# Power_Board.net
KiCad netlist of a schematic drawn in EAGLE
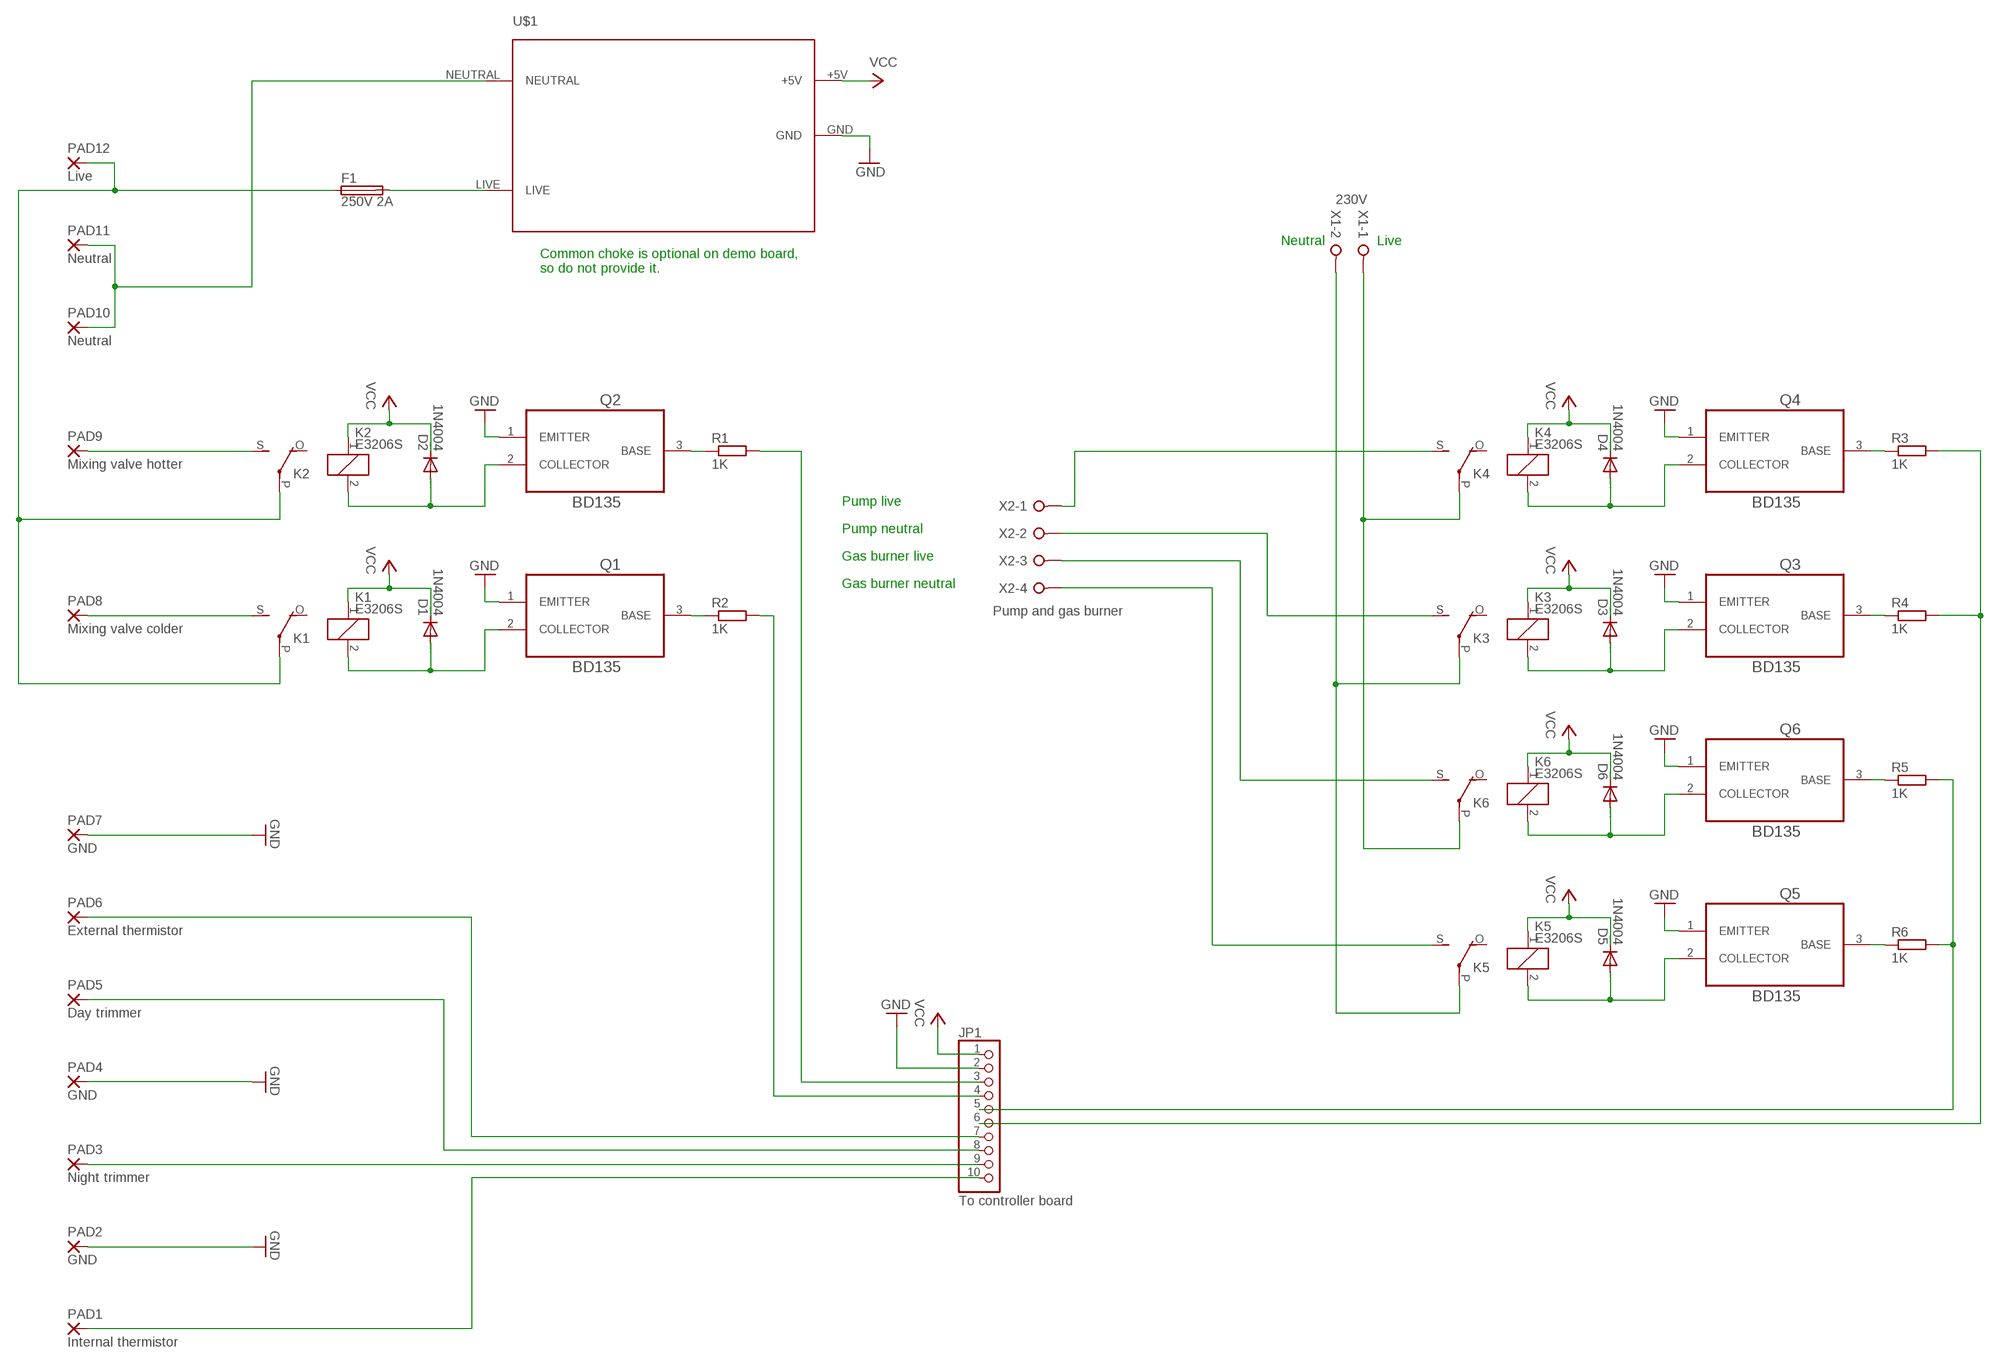
[diagram p0: schematic, sheet 1]

(export (version "E")
  (design (tool "Eeschema 10.0.6"))
  (components
    (comp (ref "D1")
      (value "1N4004")
      (footprint "eagle-import:DO41-10")
      (libsource (lib "eagle-import") (part "1N4004"))
    )
    (comp (ref "D2")
      (value "1N4004")
      (footprint "eagle-import:DO41-10")
      (libsource (lib "eagle-import") (part "1N4004"))
    )
    (comp (ref "D3")
      (value "1N4004")
      (footprint "eagle-import:DO41-10")
      (libsource (lib "eagle-import") (part "1N4004"))
    )
    (comp (ref "D4")
      (value "1N4004")
      (footprint "eagle-import:DO41-10")
      (libsource (lib "eagle-import") (part "1N4004"))
    )
    (comp (ref "D5")
      (value "1N4004")
      (footprint "eagle-import:DO41-10")
      (libsource (lib "eagle-import") (part "1N4004"))
    )
    (comp (ref "D6")
      (value "1N4004")
      (footprint "eagle-import:DO41-10")
      (libsource (lib "eagle-import") (part "1N4004"))
    )
    (comp (ref "F1")
      (value "250V 2A")
      (footprint "eagle-import:GSH15")
      (fields (field (name "MPN") "64900001039"))
      (libsource (lib "eagle-import") (part "GSH15"))
    )
    (comp (ref "JP1")
      (value "To controller board")
      (footprint "eagle-import:1X10")
      (libsource (lib "eagle-import") (part "PINHD-1X10"))
    )
    (comp (ref "K1")
      (value "E3206S")
      (footprint "eagle-import:E3206S")
      (libsource (lib "eagle-import") (part "E3206S"))
    )
    (comp (ref "K2")
      (value "E3206S")
      (footprint "eagle-import:E3206S")
      (libsource (lib "eagle-import") (part "E3206S"))
    )
    (comp (ref "K3")
      (value "E3206S")
      (footprint "eagle-import:E3206S")
      (libsource (lib "eagle-import") (part "E3206S"))
    )
    (comp (ref "K4")
      (value "E3206S")
      (footprint "eagle-import:E3206S")
      (libsource (lib "eagle-import") (part "E3206S"))
    )
    (comp (ref "K5")
      (value "E3206S")
      (footprint "eagle-import:E3206S")
      (libsource (lib "eagle-import") (part "E3206S"))
    )
    (comp (ref "K6")
      (value "E3206S")
      (footprint "eagle-import:E3206S")
      (libsource (lib "eagle-import") (part "E3206S"))
    )
    (comp (ref "PAD1")
      (value "Internal thermistor")
      (footprint "eagle-import:SMD2,54-20,32")
      (libsource (lib "eagle-import") (part "SMD20"))
    )
    (comp (ref "PAD2")
      (value "GND")
      (footprint "eagle-import:SMD2,54-20,32")
      (libsource (lib "eagle-import") (part "SMD20"))
    )
    (comp (ref "PAD3")
      (value "Night trimmer")
      (footprint "eagle-import:SMD2,54-20,32")
      (libsource (lib "eagle-import") (part "SMD20"))
    )
    (comp (ref "PAD4")
      (value "GND")
      (footprint "eagle-import:SMD2,54-20,32")
      (libsource (lib "eagle-import") (part "SMD20"))
    )
    (comp (ref "PAD5")
      (value "Day trimmer")
      (footprint "eagle-import:SMD2,54-20,32")
      (libsource (lib "eagle-import") (part "SMD20"))
    )
    (comp (ref "PAD6")
      (value "External thermistor")
      (footprint "eagle-import:SMD2,54-20,32")
      (libsource (lib "eagle-import") (part "SMD20"))
    )
    (comp (ref "PAD7")
      (value "GND")
      (footprint "eagle-import:SMD2,54-20,32")
      (libsource (lib "eagle-import") (part "SMD20"))
    )
    (comp (ref "PAD8")
      (value "Mixing valve colder")
      (footprint "eagle-import:SMD2,54-20,32")
      (libsource (lib "eagle-import") (part "SMD20"))
    )
    (comp (ref "PAD9")
      (value "Mixing valve hotter")
      (footprint "eagle-import:SMD2,54-20,32")
      (libsource (lib "eagle-import") (part "SMD20"))
    )
    (comp (ref "PAD10")
      (value "Neutral")
      (footprint "eagle-import:SMD2,54-20,32")
      (libsource (lib "eagle-import") (part "SMD20"))
    )
    (comp (ref "PAD11")
      (value "Neutral")
      (footprint "eagle-import:SMD2,54-20,32")
      (libsource (lib "eagle-import") (part "SMD20"))
    )
    (comp (ref "PAD12")
      (value "Live")
      (footprint "eagle-import:SMD2,54-20,32")
      (libsource (lib "eagle-import") (part "SMD20"))
    )
    (comp (ref "Q1")
      (value "BD135")
      (footprint "eagle-import:TRANS_BD135")
      (fields (field (name "MPN") "    BD135"))
      (libsource (lib "eagle-import") (part "BD135"))
    )
    (comp (ref "Q2")
      (value "BD135")
      (footprint "eagle-import:TRANS_BD135")
      (fields (field (name "MPN") "    BD135"))
      (libsource (lib "eagle-import") (part "BD135"))
    )
    (comp (ref "Q3")
      (value "BD135")
      (footprint "eagle-import:TRANS_BD135")
      (fields (field (name "MPN") "    BD135"))
      (libsource (lib "eagle-import") (part "BD135"))
    )
    (comp (ref "Q4")
      (value "BD135")
      (footprint "eagle-import:TRANS_BD135")
      (fields (field (name "MPN") "    BD135"))
      (libsource (lib "eagle-import") (part "BD135"))
    )
    (comp (ref "Q5")
      (value "BD135")
      (footprint "eagle-import:TRANS_BD135")
      (fields (field (name "MPN") "    BD135"))
      (libsource (lib "eagle-import") (part "BD135"))
    )
    (comp (ref "Q6")
      (value "BD135")
      (footprint "eagle-import:TRANS_BD135")
      (fields (field (name "MPN") "    BD135"))
      (libsource (lib "eagle-import") (part "BD135"))
    )
    (comp (ref "R1")
      (value "1K")
      (footprint "eagle-import:0207_10")
      (libsource (lib "eagle-import") (part "R-EU_0207/10"))
    )
    (comp (ref "R2")
      (value "1K")
      (footprint "eagle-import:0207_10")
      (libsource (lib "eagle-import") (part "R-EU_0207/10"))
    )
    (comp (ref "R3")
      (value "1K")
      (footprint "eagle-import:0207_10")
      (libsource (lib "eagle-import") (part "R-EU_0207/10"))
    )
    (comp (ref "R4")
      (value "1K")
      (footprint "eagle-import:0207_10")
      (libsource (lib "eagle-import") (part "R-EU_0207/10"))
    )
    (comp (ref "R5")
      (value "1K")
      (footprint "eagle-import:0207_10")
      (libsource (lib "eagle-import") (part "R-EU_0207/10"))
    )
    (comp (ref "R6")
      (value "1K")
      (footprint "eagle-import:0207_10")
      (libsource (lib "eagle-import") (part "R-EU_0207/10"))
    )
    (comp (ref "U$1")
      (value "VTX-214-010-205")
      (footprint "eagle-import:VTX-214-010-205")
      (libsource (lib "eagle-import") (part "VTX-214-010-205"))
    )
    (comp (ref "X1")
      (value "230V")
      (footprint "eagle-import:W237-132")
      (libsource (lib "eagle-import") (part "W237-02P"))
    )
    (comp (ref "X2")
      (value "Pump and gas burner")
      (footprint "eagle-import:W237-4P")
      (libsource (lib "eagle-import") (part "W237-04P"))
    )
  )
  (nets
    (net (code "1") (name "GND") (class "Default")
      (node (ref "JP1") (pin "2") (pinfunction "2_2") (pintype "passive"))
      (node (ref "PAD2") (pin "1") (pinfunction "P_1") (pintype "passive"))
      (node (ref "PAD4") (pin "1") (pinfunction "P_1") (pintype "passive"))
      (node (ref "PAD7") (pin "1") (pinfunction "P_1") (pintype "passive"))
      (node (ref "Q1") (pin "1") (pinfunction "EMITTER_1") (pintype "passive"))
      (node (ref "Q2") (pin "1") (pinfunction "EMITTER_1") (pintype "passive"))
      (node (ref "Q3") (pin "1") (pinfunction "EMITTER_1") (pintype "passive"))
      (node (ref "Q4") (pin "1") (pinfunction "EMITTER_1") (pintype "passive"))
      (node (ref "Q5") (pin "1") (pinfunction "EMITTER_1") (pintype "passive"))
      (node (ref "Q6") (pin "1") (pinfunction "EMITTER_1") (pintype "passive"))
      (node (ref "U$1") (pin "GND") (pinfunction "GND_GND") (pintype "power_in"))
    )
    (net (code "2") (name "Net-(F1-Pad2)") (class "Default")
      (node (ref "F1") (pin "2") (pinfunction "2_2") (pintype "passive"))
      (node (ref "U$1") (pin "LIVE") (pinfunction "LIVE_LIVE") (pintype "power_in"))
    )
    (net (code "3") (name "Net-(JP1-Pad3)") (class "Default")
      (node (ref "JP1") (pin "3") (pinfunction "3_3") (pintype "passive"))
      (node (ref "R1") (pin "2") (pinfunction "2_2") (pintype "passive"))
    )
    (net (code "4") (name "Net-(JP1-Pad4)") (class "Default")
      (node (ref "JP1") (pin "4") (pinfunction "4_4") (pintype "passive"))
      (node (ref "R2") (pin "2") (pinfunction "2_2") (pintype "passive"))
    )
    (net (code "5") (name "Net-(JP1-Pad5)") (class "Default")
      (node (ref "JP1") (pin "5") (pinfunction "5_5") (pintype "passive"))
      (node (ref "R5") (pin "2") (pinfunction "2_2") (pintype "passive"))
      (node (ref "R6") (pin "2") (pinfunction "2_2") (pintype "passive"))
    )
    (net (code "6") (name "Net-(JP1-Pad6)") (class "Default")
      (node (ref "JP1") (pin "6") (pinfunction "6_6") (pintype "passive"))
      (node (ref "R3") (pin "2") (pinfunction "2_2") (pintype "passive"))
      (node (ref "R4") (pin "2") (pinfunction "2_2") (pintype "passive"))
    )
    (net (code "7") (name "Net-(PAD1-P)") (class "Default")
      (node (ref "JP1") (pin "10") (pinfunction "10_10") (pintype "passive"))
      (node (ref "PAD1") (pin "1") (pinfunction "P_1") (pintype "passive"))
    )
    (net (code "8") (name "Net-(PAD3-P)") (class "Default")
      (node (ref "JP1") (pin "9") (pinfunction "9_9") (pintype "passive"))
      (node (ref "PAD3") (pin "1") (pinfunction "P_1") (pintype "passive"))
    )
    (net (code "9") (name "Net-(PAD5-P)") (class "Default")
      (node (ref "JP1") (pin "8") (pinfunction "8_8") (pintype "passive"))
      (node (ref "PAD5") (pin "1") (pinfunction "P_1") (pintype "passive"))
    )
    (net (code "10") (name "Net-(PAD6-P)") (class "Default")
      (node (ref "JP1") (pin "7") (pinfunction "7_7") (pintype "passive"))
      (node (ref "PAD6") (pin "1") (pinfunction "P_1") (pintype "passive"))
    )
    (net (code "11") (name "Net-(PAD8-P)") (class "Default")
      (node (ref "K1") (pin "S") (pinfunction "S_S") (pintype "passive"))
      (node (ref "PAD8") (pin "1") (pinfunction "P_1") (pintype "passive"))
    )
    (net (code "12") (name "Net-(PAD9-P)") (class "Default")
      (node (ref "K2") (pin "S") (pinfunction "S_S") (pintype "passive"))
      (node (ref "PAD9") (pin "1") (pinfunction "P_1") (pintype "passive"))
    )
    (net (code "13") (name "Net-(PAD10-P)") (class "Default")
      (node (ref "PAD10") (pin "1") (pinfunction "P_1") (pintype "passive"))
      (node (ref "PAD11") (pin "1") (pinfunction "P_1") (pintype "passive"))
      (node (ref "U$1") (pin "NEUTRAL") (pinfunction "NEUTRAL_NEUTRAL") (pintype "power_in"))
    )
    (net (code "14") (name "Net-(PAD12-P)") (class "Default")
      (node (ref "F1") (pin "1") (pinfunction "1_1") (pintype "passive"))
      (node (ref "K1") (pin "P") (pinfunction "P_P") (pintype "passive"))
      (node (ref "K2") (pin "P") (pinfunction "P_P") (pintype "passive"))
      (node (ref "PAD12") (pin "1") (pinfunction "P_1") (pintype "passive"))
    )
    (net (code "15") (name "Net-(Q1-BASE)") (class "Default")
      (node (ref "Q1") (pin "3") (pinfunction "BASE_3") (pintype "passive"))
      (node (ref "R2") (pin "1") (pinfunction "1_1") (pintype "passive"))
    )
    (net (code "16") (name "Net-(Q1-COLLECTOR)") (class "Default")
      (node (ref "D1") (pin "A") (pinfunction "A_A") (pintype "passive"))
      (node (ref "K1") (pin "2") (pinfunction "2_2") (pintype "passive"))
      (node (ref "Q1") (pin "2") (pinfunction "COLLECTOR_2") (pintype "passive"))
    )
    (net (code "17") (name "Net-(Q2-BASE)") (class "Default")
      (node (ref "Q2") (pin "3") (pinfunction "BASE_3") (pintype "passive"))
      (node (ref "R1") (pin "1") (pinfunction "1_1") (pintype "passive"))
    )
    (net (code "18") (name "Net-(Q2-COLLECTOR)") (class "Default")
      (node (ref "D2") (pin "A") (pinfunction "A_A") (pintype "passive"))
      (node (ref "K2") (pin "2") (pinfunction "2_2") (pintype "passive"))
      (node (ref "Q2") (pin "2") (pinfunction "COLLECTOR_2") (pintype "passive"))
    )
    (net (code "19") (name "Net-(Q3-BASE)") (class "Default")
      (node (ref "Q3") (pin "3") (pinfunction "BASE_3") (pintype "passive"))
      (node (ref "R4") (pin "1") (pinfunction "1_1") (pintype "passive"))
    )
    (net (code "20") (name "Net-(Q3-COLLECTOR)") (class "Default")
      (node (ref "D3") (pin "A") (pinfunction "A_A") (pintype "passive"))
      (node (ref "K3") (pin "2") (pinfunction "2_2") (pintype "passive"))
      (node (ref "Q3") (pin "2") (pinfunction "COLLECTOR_2") (pintype "passive"))
    )
    (net (code "21") (name "Net-(Q4-BASE)") (class "Default")
      (node (ref "Q4") (pin "3") (pinfunction "BASE_3") (pintype "passive"))
      (node (ref "R3") (pin "1") (pinfunction "1_1") (pintype "passive"))
    )
    (net (code "22") (name "Net-(Q4-COLLECTOR)") (class "Default")
      (node (ref "D4") (pin "A") (pinfunction "A_A") (pintype "passive"))
      (node (ref "K4") (pin "2") (pinfunction "2_2") (pintype "passive"))
      (node (ref "Q4") (pin "2") (pinfunction "COLLECTOR_2") (pintype "passive"))
    )
    (net (code "23") (name "Net-(Q5-BASE)") (class "Default")
      (node (ref "Q5") (pin "3") (pinfunction "BASE_3") (pintype "passive"))
      (node (ref "R6") (pin "1") (pinfunction "1_1") (pintype "passive"))
    )
    (net (code "24") (name "Net-(Q5-COLLECTOR)") (class "Default")
      (node (ref "D5") (pin "A") (pinfunction "A_A") (pintype "passive"))
      (node (ref "K5") (pin "2") (pinfunction "2_2") (pintype "passive"))
      (node (ref "Q5") (pin "2") (pinfunction "COLLECTOR_2") (pintype "passive"))
    )
    (net (code "25") (name "Net-(Q6-BASE)") (class "Default")
      (node (ref "Q6") (pin "3") (pinfunction "BASE_3") (pintype "passive"))
      (node (ref "R5") (pin "1") (pinfunction "1_1") (pintype "passive"))
    )
    (net (code "26") (name "Net-(Q6-COLLECTOR)") (class "Default")
      (node (ref "D6") (pin "A") (pinfunction "A_A") (pintype "passive"))
      (node (ref "K6") (pin "2") (pinfunction "2_2") (pintype "passive"))
      (node (ref "Q6") (pin "2") (pinfunction "COLLECTOR_2") (pintype "passive"))
    )
    (net (code "27") (name "Net-(X1A-KL)") (class "Default")
      (node (ref "K4") (pin "P") (pinfunction "P_P") (pintype "passive"))
      (node (ref "K6") (pin "P") (pinfunction "P_P") (pintype "passive"))
      (node (ref "X1") (pin "1") (pinfunction "KL_1") (pintype "passive"))
    )
    (net (code "28") (name "Net-(X1B-KL)") (class "Default")
      (node (ref "K3") (pin "P") (pinfunction "P_P") (pintype "passive"))
      (node (ref "K5") (pin "P") (pinfunction "P_P") (pintype "passive"))
      (node (ref "X1") (pin "2") (pinfunction "KL_2") (pintype "passive"))
    )
    (net (code "29") (name "Net-(X2A-KL)") (class "Default")
      (node (ref "K4") (pin "S") (pinfunction "S_S") (pintype "passive"))
      (node (ref "X2") (pin "1") (pinfunction "KL_1") (pintype "passive"))
    )
    (net (code "30") (name "Net-(X2B-KL)") (class "Default")
      (node (ref "K3") (pin "S") (pinfunction "S_S") (pintype "passive"))
      (node (ref "X2") (pin "2") (pinfunction "KL_2") (pintype "passive"))
    )
    (net (code "31") (name "Net-(X2C-KL)") (class "Default")
      (node (ref "K6") (pin "S") (pinfunction "S_S") (pintype "passive"))
      (node (ref "X2") (pin "3") (pinfunction "KL_3") (pintype "passive"))
    )
    (net (code "32") (name "Net-(X2D-KL)") (class "Default")
      (node (ref "K5") (pin "S") (pinfunction "S_S") (pintype "passive"))
      (node (ref "X2") (pin "4") (pinfunction "KL_4") (pintype "passive"))
    )
    (net (code "33") (name "VCC") (class "Default")
      (node (ref "D1") (pin "C") (pinfunction "C_C") (pintype "passive"))
      (node (ref "D2") (pin "C") (pinfunction "C_C") (pintype "passive"))
      (node (ref "D3") (pin "C") (pinfunction "C_C") (pintype "passive"))
      (node (ref "D4") (pin "C") (pinfunction "C_C") (pintype "passive"))
      (node (ref "D5") (pin "C") (pinfunction "C_C") (pintype "passive"))
      (node (ref "D6") (pin "C") (pinfunction "C_C") (pintype "passive"))
      (node (ref "JP1") (pin "1") (pinfunction "1_1") (pintype "passive"))
      (node (ref "K1") (pin "1") (pinfunction "1_1") (pintype "passive"))
      (node (ref "K2") (pin "1") (pinfunction "1_1") (pintype "passive"))
      (node (ref "K3") (pin "1") (pinfunction "1_1") (pintype "passive"))
      (node (ref "K4") (pin "1") (pinfunction "1_1") (pintype "passive"))
      (node (ref "K5") (pin "1") (pinfunction "1_1") (pintype "passive"))
      (node (ref "K6") (pin "1") (pinfunction "1_1") (pintype "passive"))
      (node (ref "U$1") (pin "+5V") (pinfunction "+5V_+5V") (pintype "power_in"))
    )
    (net (code "34") (name "unconnected-(K1-PadO)") (class "Default")
      (node (ref "K1") (pin "O") (pinfunction "O_O") (pintype "passive"))
    )
    (net (code "35") (name "unconnected-(K2-PadO)") (class "Default")
      (node (ref "K2") (pin "O") (pinfunction "O_O") (pintype "passive"))
    )
    (net (code "36") (name "unconnected-(K3-PadO)") (class "Default")
      (node (ref "K3") (pin "O") (pinfunction "O_O") (pintype "passive"))
    )
    (net (code "37") (name "unconnected-(K4-PadO)") (class "Default")
      (node (ref "K4") (pin "O") (pinfunction "O_O") (pintype "passive"))
    )
    (net (code "38") (name "unconnected-(K5-PadO)") (class "Default")
      (node (ref "K5") (pin "O") (pinfunction "O_O") (pintype "passive"))
    )
    (net (code "39") (name "unconnected-(K6-PadO)") (class "Default")
      (node (ref "K6") (pin "O") (pinfunction "O_O") (pintype "passive"))
    )
  )
)
